# XY_RJ12_breakout.net
KiCad netlist of a schematic drawn in EAGLE
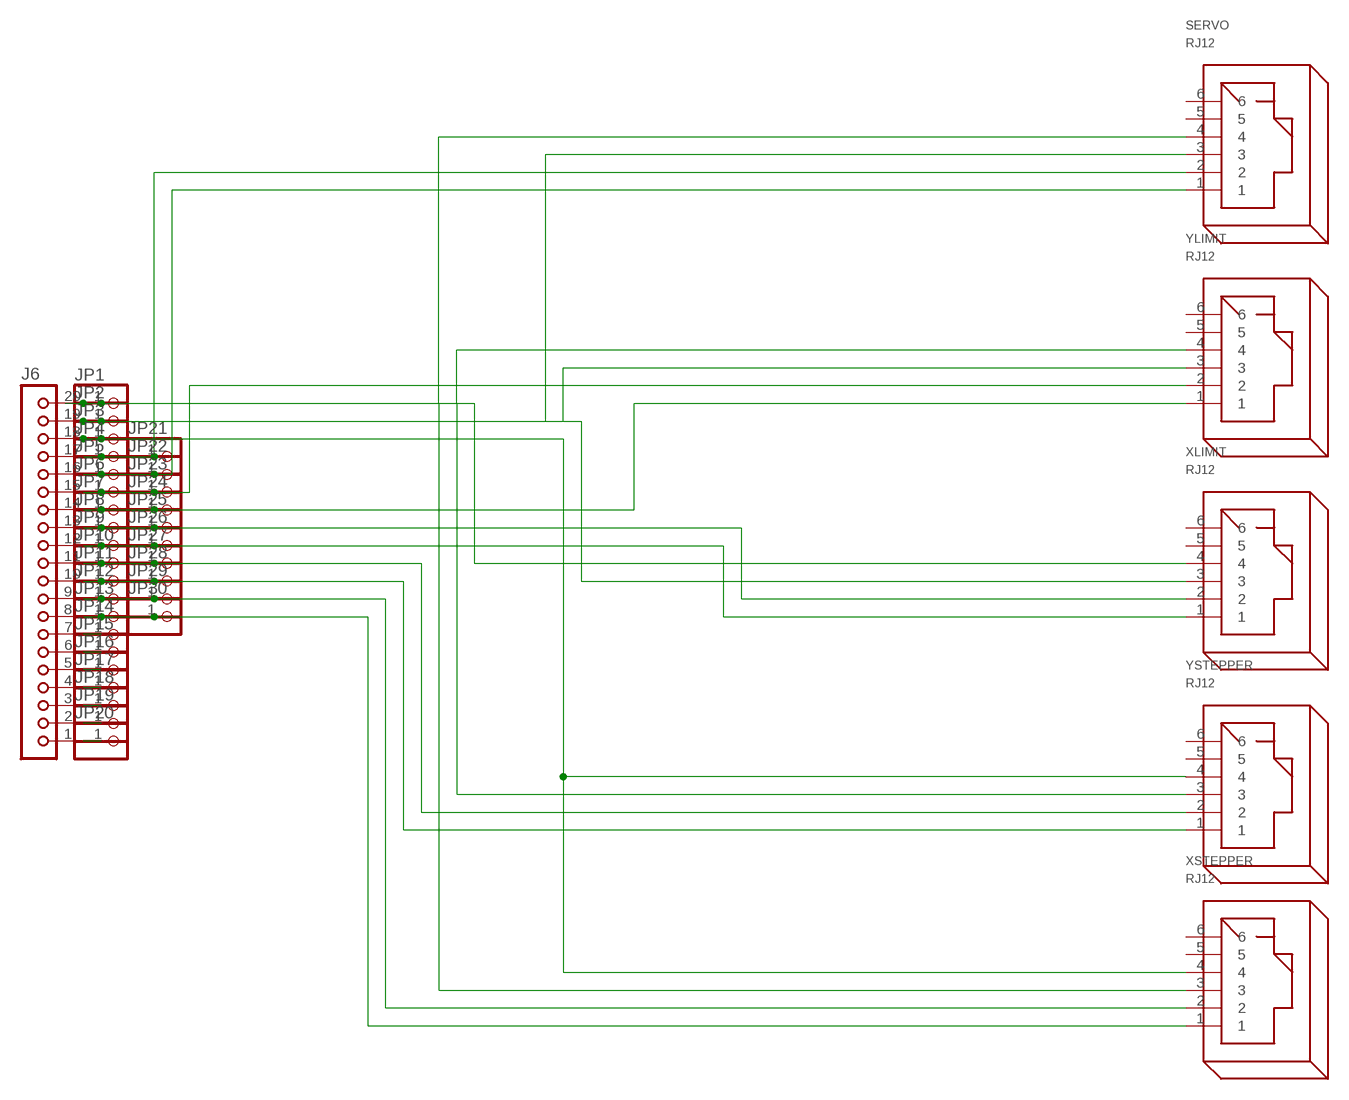
[diagram p0: schematic, sheet 1]

(export (version "E")
  (design (tool "Eeschema 10.0.6"))
  (components
    (comp (ref "J6")
      (value "JBK20")
      (footprint "eagle-import:JBK20")
      (libsource (lib "eagle-import") (part "JBK20"))
    )
    (comp (ref "JP1")
      (value "PINHD-1X1")
      (footprint "eagle-import:1X01")
      (libsource (lib "eagle-import") (part "PINHD-1X1"))
    )
    (comp (ref "JP2")
      (value "PINHD-1X1")
      (footprint "eagle-import:1X01")
      (libsource (lib "eagle-import") (part "PINHD-1X1"))
    )
    (comp (ref "JP3")
      (value "PINHD-1X1")
      (footprint "eagle-import:1X01")
      (libsource (lib "eagle-import") (part "PINHD-1X1"))
    )
    (comp (ref "JP4")
      (value "PINHD-1X1")
      (footprint "eagle-import:1X01")
      (libsource (lib "eagle-import") (part "PINHD-1X1"))
    )
    (comp (ref "JP5")
      (value "PINHD-1X1")
      (footprint "eagle-import:1X01")
      (libsource (lib "eagle-import") (part "PINHD-1X1"))
    )
    (comp (ref "JP6")
      (value "PINHD-1X1")
      (footprint "eagle-import:1X01")
      (libsource (lib "eagle-import") (part "PINHD-1X1"))
    )
    (comp (ref "JP7")
      (value "PINHD-1X1")
      (footprint "eagle-import:1X01")
      (libsource (lib "eagle-import") (part "PINHD-1X1"))
    )
    (comp (ref "JP8")
      (value "PINHD-1X1")
      (footprint "eagle-import:1X01")
      (libsource (lib "eagle-import") (part "PINHD-1X1"))
    )
    (comp (ref "JP9")
      (value "PINHD-1X1")
      (footprint "eagle-import:1X01")
      (libsource (lib "eagle-import") (part "PINHD-1X1"))
    )
    (comp (ref "JP10")
      (value "PINHD-1X1")
      (footprint "eagle-import:1X01")
      (libsource (lib "eagle-import") (part "PINHD-1X1"))
    )
    (comp (ref "JP11")
      (value "PINHD-1X1")
      (footprint "eagle-import:1X01")
      (libsource (lib "eagle-import") (part "PINHD-1X1"))
    )
    (comp (ref "JP12")
      (value "PINHD-1X1")
      (footprint "eagle-import:1X01")
      (libsource (lib "eagle-import") (part "PINHD-1X1"))
    )
    (comp (ref "JP13")
      (value "PINHD-1X1")
      (footprint "eagle-import:1X01")
      (libsource (lib "eagle-import") (part "PINHD-1X1"))
    )
    (comp (ref "JP14")
      (value "PINHD-1X1")
      (footprint "eagle-import:1X01")
      (libsource (lib "eagle-import") (part "PINHD-1X1"))
    )
    (comp (ref "JP15")
      (value "PINHD-1X1")
      (footprint "eagle-import:1X01")
      (libsource (lib "eagle-import") (part "PINHD-1X1"))
    )
    (comp (ref "JP16")
      (value "PINHD-1X1")
      (footprint "eagle-import:1X01")
      (libsource (lib "eagle-import") (part "PINHD-1X1"))
    )
    (comp (ref "JP17")
      (value "PINHD-1X1")
      (footprint "eagle-import:1X01")
      (libsource (lib "eagle-import") (part "PINHD-1X1"))
    )
    (comp (ref "JP18")
      (value "PINHD-1X1")
      (footprint "eagle-import:1X01")
      (libsource (lib "eagle-import") (part "PINHD-1X1"))
    )
    (comp (ref "JP19")
      (value "PINHD-1X1")
      (footprint "eagle-import:1X01")
      (libsource (lib "eagle-import") (part "PINHD-1X1"))
    )
    (comp (ref "JP20")
      (value "PINHD-1X1")
      (footprint "eagle-import:1X01")
      (libsource (lib "eagle-import") (part "PINHD-1X1"))
    )
    (comp (ref "JP21")
      (value "PINHD-1X1")
      (footprint "eagle-import:1X01")
      (libsource (lib "eagle-import") (part "PINHD-1X1"))
    )
    (comp (ref "JP22")
      (value "PINHD-1X1")
      (footprint "eagle-import:1X01")
      (libsource (lib "eagle-import") (part "PINHD-1X1"))
    )
    (comp (ref "JP23")
      (value "PINHD-1X1")
      (footprint "eagle-import:1X01")
      (libsource (lib "eagle-import") (part "PINHD-1X1"))
    )
    (comp (ref "JP24")
      (value "PINHD-1X1")
      (footprint "eagle-import:1X01")
      (libsource (lib "eagle-import") (part "PINHD-1X1"))
    )
    (comp (ref "JP25")
      (value "PINHD-1X1")
      (footprint "eagle-import:1X01")
      (libsource (lib "eagle-import") (part "PINHD-1X1"))
    )
    (comp (ref "JP26")
      (value "PINHD-1X1")
      (footprint "eagle-import:1X01")
      (libsource (lib "eagle-import") (part "PINHD-1X1"))
    )
    (comp (ref "JP27")
      (value "PINHD-1X1")
      (footprint "eagle-import:1X01")
      (libsource (lib "eagle-import") (part "PINHD-1X1"))
    )
    (comp (ref "JP28")
      (value "PINHD-1X1")
      (footprint "eagle-import:1X01")
      (libsource (lib "eagle-import") (part "PINHD-1X1"))
    )
    (comp (ref "JP29")
      (value "PINHD-1X1")
      (footprint "eagle-import:1X01")
      (libsource (lib "eagle-import") (part "PINHD-1X1"))
    )
    (comp (ref "JP30")
      (value "PINHD-1X1")
      (footprint "eagle-import:1X01")
      (libsource (lib "eagle-import") (part "PINHD-1X1"))
    )
    (comp (ref "SERVO")
      (value "RJ12")
      (footprint "eagle-import:RJ12")
      (libsource (lib "eagle-import") (part "RJ12"))
    )
    (comp (ref "XLIMIT")
      (value "RJ12")
      (footprint "eagle-import:RJ12")
      (libsource (lib "eagle-import") (part "RJ12"))
    )
    (comp (ref "XSTEPPER")
      (value "RJ12")
      (footprint "eagle-import:RJ12")
      (libsource (lib "eagle-import") (part "RJ12"))
    )
    (comp (ref "YLIMIT")
      (value "RJ12")
      (footprint "eagle-import:RJ12")
      (libsource (lib "eagle-import") (part "RJ12"))
    )
    (comp (ref "YSTEPPER")
      (value "RJ12")
      (footprint "eagle-import:RJ12")
      (libsource (lib "eagle-import") (part "RJ12"))
    )
  )
  (nets
    (net (code "1") (name "Net-(J6-Pad1)") (class "Default")
      (node (ref "J6") (pin "1") (pinfunction "1_1") (pintype "passive"))
      (node (ref "JP20") (pin "1") (pinfunction "1_1") (pintype "passive"))
    )
    (net (code "2") (name "Net-(J6-Pad2)") (class "Default")
      (node (ref "J6") (pin "2") (pinfunction "2_2") (pintype "passive"))
      (node (ref "JP19") (pin "1") (pinfunction "1_1") (pintype "passive"))
    )
    (net (code "3") (name "Net-(J6-Pad3)") (class "Default")
      (node (ref "J6") (pin "3") (pinfunction "3_3") (pintype "passive"))
      (node (ref "JP18") (pin "1") (pinfunction "1_1") (pintype "passive"))
    )
    (net (code "4") (name "Net-(J6-Pad4)") (class "Default")
      (node (ref "J6") (pin "4") (pinfunction "4_4") (pintype "passive"))
      (node (ref "JP17") (pin "1") (pinfunction "1_1") (pintype "passive"))
    )
    (net (code "5") (name "Net-(J6-Pad5)") (class "Default")
      (node (ref "J6") (pin "5") (pinfunction "5_5") (pintype "passive"))
      (node (ref "JP16") (pin "1") (pinfunction "1_1") (pintype "passive"))
    )
    (net (code "6") (name "Net-(J6-Pad6)") (class "Default")
      (node (ref "J6") (pin "6") (pinfunction "6_6") (pintype "passive"))
      (node (ref "JP15") (pin "1") (pinfunction "1_1") (pintype "passive"))
    )
    (net (code "7") (name "Net-(J6-Pad7)") (class "Default")
      (node (ref "J6") (pin "7") (pinfunction "7_7") (pintype "passive"))
      (node (ref "JP14") (pin "1") (pinfunction "1_1") (pintype "passive"))
    )
    (net (code "8") (name "Net-(J6-Pad8)") (class "Default")
      (node (ref "J6") (pin "8") (pinfunction "8_8") (pintype "passive"))
      (node (ref "JP13") (pin "1") (pinfunction "1_1") (pintype "passive"))
      (node (ref "JP30") (pin "1") (pinfunction "1_1") (pintype "passive"))
      (node (ref "XSTEPPER") (pin "1") (pinfunction "1_1") (pintype "bidirectional"))
    )
    (net (code "9") (name "Net-(J6-Pad9)") (class "Default")
      (node (ref "J6") (pin "9") (pinfunction "9_9") (pintype "passive"))
      (node (ref "JP12") (pin "1") (pinfunction "1_1") (pintype "passive"))
      (node (ref "JP29") (pin "1") (pinfunction "1_1") (pintype "passive"))
      (node (ref "XSTEPPER") (pin "2") (pinfunction "2_2") (pintype "bidirectional"))
    )
    (net (code "10") (name "Net-(J6-Pad10)") (class "Default")
      (node (ref "J6") (pin "10") (pinfunction "10_10") (pintype "passive"))
      (node (ref "JP11") (pin "1") (pinfunction "1_1") (pintype "passive"))
      (node (ref "JP28") (pin "1") (pinfunction "1_1") (pintype "passive"))
      (node (ref "YSTEPPER") (pin "1") (pinfunction "1_1") (pintype "bidirectional"))
    )
    (net (code "11") (name "Net-(J6-Pad11)") (class "Default")
      (node (ref "J6") (pin "11") (pinfunction "11_11") (pintype "passive"))
      (node (ref "JP10") (pin "1") (pinfunction "1_1") (pintype "passive"))
      (node (ref "JP27") (pin "1") (pinfunction "1_1") (pintype "passive"))
      (node (ref "YSTEPPER") (pin "2") (pinfunction "2_2") (pintype "bidirectional"))
    )
    (net (code "12") (name "Net-(J6-Pad12)") (class "Default")
      (node (ref "J6") (pin "12") (pinfunction "12_12") (pintype "passive"))
      (node (ref "JP26") (pin "1") (pinfunction "1_1") (pintype "passive"))
      (node (ref "JP9") (pin "1") (pinfunction "1_1") (pintype "passive"))
      (node (ref "XLIMIT") (pin "1") (pinfunction "1_1") (pintype "bidirectional"))
    )
    (net (code "13") (name "Net-(J6-Pad13)") (class "Default")
      (node (ref "J6") (pin "13") (pinfunction "13_13") (pintype "passive"))
      (node (ref "JP25") (pin "1") (pinfunction "1_1") (pintype "passive"))
      (node (ref "JP8") (pin "1") (pinfunction "1_1") (pintype "passive"))
      (node (ref "XLIMIT") (pin "2") (pinfunction "2_2") (pintype "bidirectional"))
    )
    (net (code "14") (name "Net-(J6-Pad14)") (class "Default")
      (node (ref "J6") (pin "14") (pinfunction "14_14") (pintype "passive"))
      (node (ref "JP24") (pin "1") (pinfunction "1_1") (pintype "passive"))
      (node (ref "JP7") (pin "1") (pinfunction "1_1") (pintype "passive"))
      (node (ref "YLIMIT") (pin "1") (pinfunction "1_1") (pintype "bidirectional"))
    )
    (net (code "15") (name "Net-(J6-Pad15)") (class "Default")
      (node (ref "J6") (pin "15") (pinfunction "15_15") (pintype "passive"))
      (node (ref "JP23") (pin "1") (pinfunction "1_1") (pintype "passive"))
      (node (ref "JP6") (pin "1") (pinfunction "1_1") (pintype "passive"))
      (node (ref "YLIMIT") (pin "2") (pinfunction "2_2") (pintype "bidirectional"))
    )
    (net (code "16") (name "Net-(J6-Pad16)") (class "Default")
      (node (ref "J6") (pin "16") (pinfunction "16_16") (pintype "passive"))
      (node (ref "JP22") (pin "1") (pinfunction "1_1") (pintype "passive"))
      (node (ref "JP5") (pin "1") (pinfunction "1_1") (pintype "passive"))
      (node (ref "SERVO") (pin "1") (pinfunction "1_1") (pintype "bidirectional"))
    )
    (net (code "17") (name "Net-(J6-Pad17)") (class "Default")
      (node (ref "J6") (pin "17") (pinfunction "17_17") (pintype "passive"))
      (node (ref "JP21") (pin "1") (pinfunction "1_1") (pintype "passive"))
      (node (ref "JP4") (pin "1") (pinfunction "1_1") (pintype "passive"))
      (node (ref "SERVO") (pin "2") (pinfunction "2_2") (pintype "bidirectional"))
    )
    (net (code "18") (name "Net-(J6-Pad18)") (class "Default")
      (node (ref "J6") (pin "18") (pinfunction "18_18") (pintype "passive"))
      (node (ref "JP3") (pin "1") (pinfunction "1_1") (pintype "passive"))
      (node (ref "XSTEPPER") (pin "4") (pinfunction "4_4") (pintype "bidirectional"))
      (node (ref "YSTEPPER") (pin "4") (pinfunction "4_4") (pintype "bidirectional"))
    )
    (net (code "19") (name "Net-(J6-Pad19)") (class "Default")
      (node (ref "J6") (pin "19") (pinfunction "19_19") (pintype "passive"))
      (node (ref "JP2") (pin "1") (pinfunction "1_1") (pintype "passive"))
      (node (ref "SERVO") (pin "3") (pinfunction "3_3") (pintype "bidirectional"))
      (node (ref "XLIMIT") (pin "3") (pinfunction "3_3") (pintype "bidirectional"))
      (node (ref "YLIMIT") (pin "3") (pinfunction "3_3") (pintype "bidirectional"))
    )
    (net (code "20") (name "Net-(J6-Pad20)") (class "Default")
      (node (ref "J6") (pin "20") (pinfunction "20_20") (pintype "passive"))
      (node (ref "JP1") (pin "1") (pinfunction "1_1") (pintype "passive"))
      (node (ref "SERVO") (pin "4") (pinfunction "4_4") (pintype "bidirectional"))
      (node (ref "XLIMIT") (pin "4") (pinfunction "4_4") (pintype "bidirectional"))
      (node (ref "XSTEPPER") (pin "3") (pinfunction "3_3") (pintype "bidirectional"))
      (node (ref "YLIMIT") (pin "4") (pinfunction "4_4") (pintype "bidirectional"))
      (node (ref "YSTEPPER") (pin "3") (pinfunction "3_3") (pintype "bidirectional"))
    )
    (net (code "21") (name "unconnected-(SERVO-Pad5)") (class "Default")
      (node (ref "SERVO") (pin "5") (pinfunction "5_5") (pintype "bidirectional"))
    )
    (net (code "22") (name "unconnected-(SERVO-Pad6)") (class "Default")
      (node (ref "SERVO") (pin "6") (pinfunction "6_6") (pintype "bidirectional"))
    )
    (net (code "23") (name "unconnected-(XLIMIT-Pad5)") (class "Default")
      (node (ref "XLIMIT") (pin "5") (pinfunction "5_5") (pintype "bidirectional"))
    )
    (net (code "24") (name "unconnected-(XLIMIT-Pad6)") (class "Default")
      (node (ref "XLIMIT") (pin "6") (pinfunction "6_6") (pintype "bidirectional"))
    )
    (net (code "25") (name "unconnected-(XSTEPPER-Pad5)") (class "Default")
      (node (ref "XSTEPPER") (pin "5") (pinfunction "5_5") (pintype "bidirectional"))
    )
    (net (code "26") (name "unconnected-(XSTEPPER-Pad6)") (class "Default")
      (node (ref "XSTEPPER") (pin "6") (pinfunction "6_6") (pintype "bidirectional"))
    )
    (net (code "27") (name "unconnected-(YLIMIT-Pad5)") (class "Default")
      (node (ref "YLIMIT") (pin "5") (pinfunction "5_5") (pintype "bidirectional"))
    )
    (net (code "28") (name "unconnected-(YLIMIT-Pad6)") (class "Default")
      (node (ref "YLIMIT") (pin "6") (pinfunction "6_6") (pintype "bidirectional"))
    )
    (net (code "29") (name "unconnected-(YSTEPPER-Pad5)") (class "Default")
      (node (ref "YSTEPPER") (pin "5") (pinfunction "5_5") (pintype "bidirectional"))
    )
    (net (code "30") (name "unconnected-(YSTEPPER-Pad6)") (class "Default")
      (node (ref "YSTEPPER") (pin "6") (pinfunction "6_6") (pintype "bidirectional"))
    )
  )
)
